# motordriver-v5_0_RC-filter.net
KiCad netlist of a schematic drawn in Altium Designer
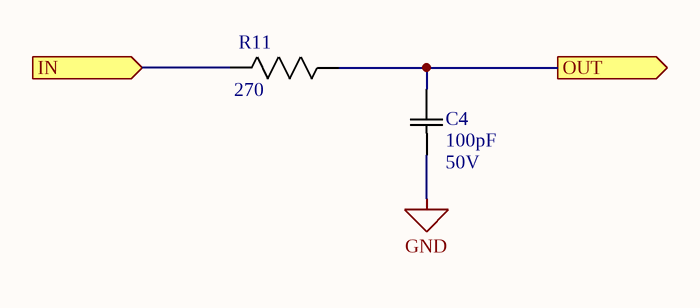
[diagram p0: motordriver-v5.0_RC-filter.SchDoc]

(export (version "E")
  (design (tool "Eeschema 10.0.6"))
  (components
    (comp (ref "C4")
      (value "100pF")
      (footprint "0603")
      (description "CAP CER 100PF 50V X7R 0603/0805")
      (fields (field (name "TOLERANCE") "10%") (field (name "RATING") "50V"))
      (libsource (lib "AltiumLibraries") (part "CAP 100pF 50V"))
    )
    (comp (ref "R11")
      (value "270")
      (footprint "0603")
      (description "RES SMD 270 OHM 1% 1/8W 0603/0805")
      (fields (field (name "TOLERANCE") "1%"))
      (libsource (lib "AltiumLibraries") (part "RES 270.0 1/8W - 1%"))
    )
  )
  (nets
    (net (code "1") (name "/IN") (class "Default")
      (node (ref "R11") (pin "2") (pinfunction "R2_2") (pintype "passive"))
    )
    (net (code "2") (name "/OUT") (class "Default")
      (node (ref "C4") (pin "2") (pinfunction "C2_2") (pintype "passive"))
      (node (ref "R11") (pin "1") (pinfunction "R1_1") (pintype "passive"))
    )
    (net (code "3") (name "GND") (class "Default")
      (node (ref "C4") (pin "1") (pinfunction "C1_1") (pintype "passive"))
    )
  )
)
